# MSP430MCU.net
KiCad netlist of a schematic drawn in Altium Designer
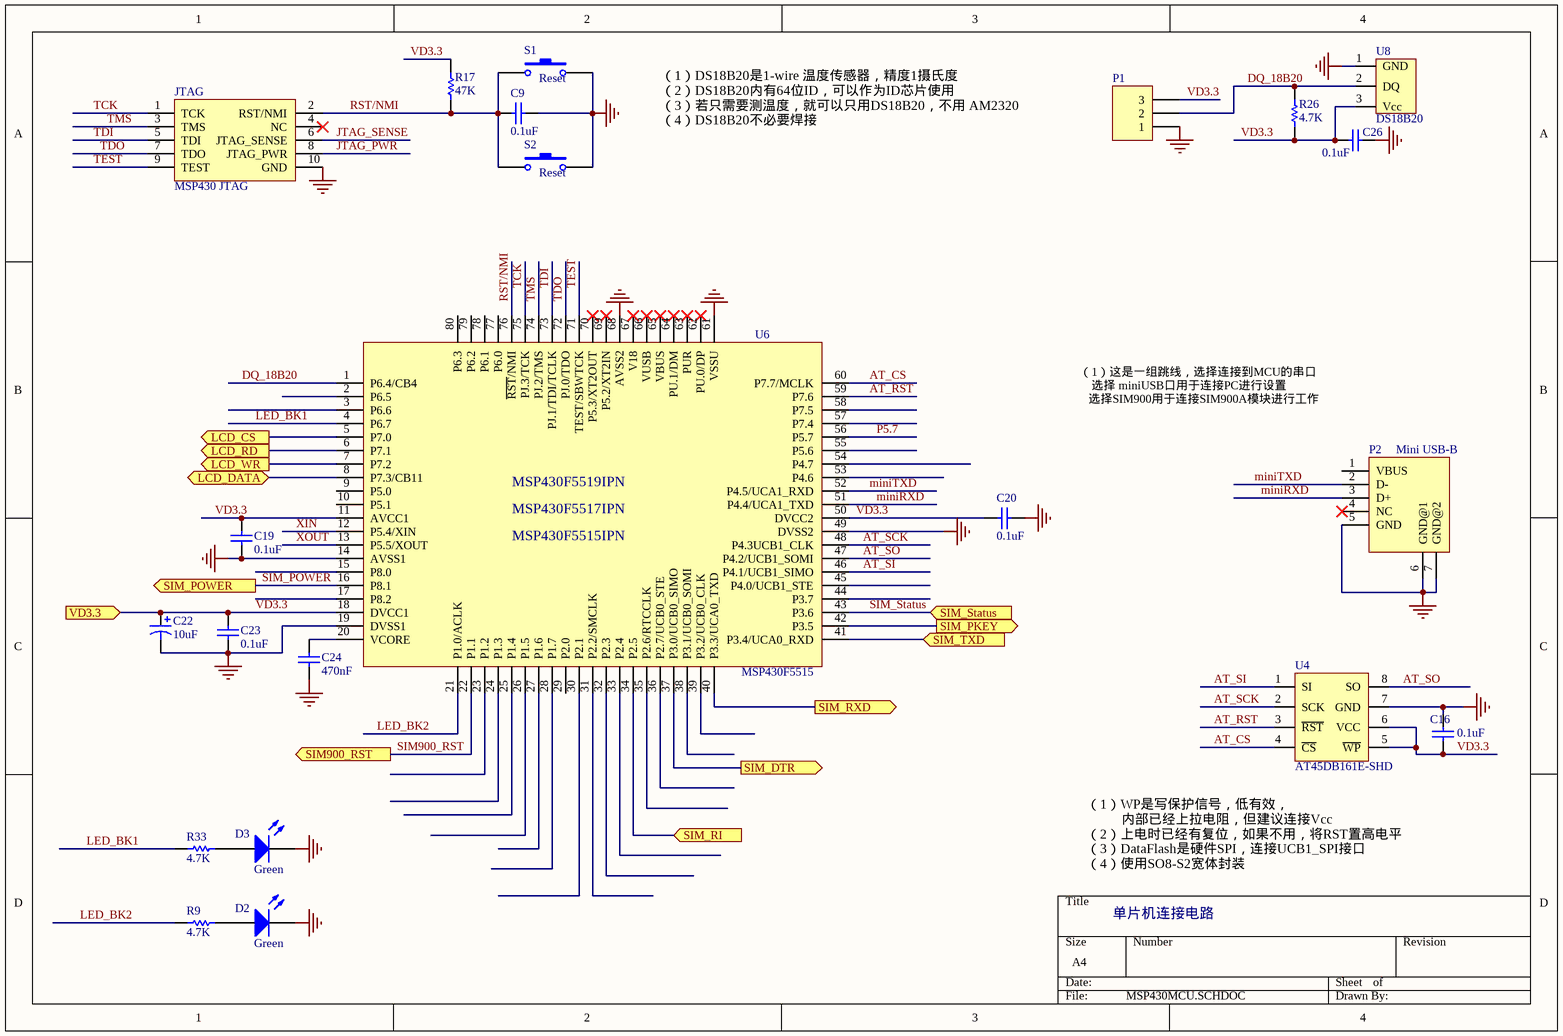
[diagram p0: MSP430MCU.SCHDOC]

(export (version "E")
  (design (tool "Eeschema 10.0.6"))
  (components
    (comp (ref "C9")
      (value "0.1uF")
      (footprint "CC1608-0603")
      (description "Capacitor (Semiconductor SIM Model)")
      (fields (field (name "Comment") "Cap Semi") (field (name "PUBLISHER") "Altium Limited"))
      (libsource (lib "Miscellaneous Devices") (part "Cap Semi"))
    )
    (comp (ref "C16")
      (value "0.1uF")
      (footprint "CC1608-0603")
      (description "Capacitor (Semiconductor SIM Model)")
      (fields (field (name "Comment") "Cap Semi") (field (name "PUBLISHER") "Altium Limited"))
      (libsource (lib "Miscellaneous Devices") (part "Cap Semi"))
    )
    (comp (ref "C19")
      (value "0.1uF")
      (footprint "CC1608-0603")
      (description "Capacitor (Semiconductor SIM Model)")
      (fields (field (name "Comment") "Cap Semi") (field (name "PUBLISHER") "Altium Limited"))
      (libsource (lib "Miscellaneous Devices") (part "Cap Semi"))
    )
    (comp (ref "C20")
      (value "0.1uF")
      (footprint "CC1608-0603")
      (description "Capacitor (Semiconductor SIM Model)")
      (fields (field (name "Comment") "Cap Semi") (field (name "PUBLISHER") "Altium Limited"))
      (libsource (lib "Miscellaneous Devices") (part "Cap Semi"))
    )
    (comp (ref "C22")
      (value "10uF")
      (footprint "CC3216-1206")
      (description "Polarized Capacitor (Surface Mount)")
      (fields (field (name "Comment") "Cap Pol3") (field (name "PUBLISHER") "Altium Limited"))
      (libsource (lib "Miscellaneous Devices") (part "Cap Pol3"))
    )
    (comp (ref "C23")
      (value "0.1uF")
      (footprint "CC1608-0603")
      (description "Capacitor (Semiconductor SIM Model)")
      (fields (field (name "Comment") "Cap Semi") (field (name "PUBLISHER") "Altium Limited"))
      (libsource (lib "Miscellaneous Devices") (part "Cap Semi"))
    )
    (comp (ref "C24")
      (value "470nF")
      (footprint "CC1608-0603")
      (description "Capacitor (Semiconductor SIM Model)")
      (fields (field (name "Comment") "Cap Semi") (field (name "PUBLISHER") "Altium Limited"))
      (libsource (lib "Miscellaneous Devices") (part "Cap Semi"))
    )
    (comp (ref "C26")
      (value "0.1uF")
      (footprint "CC1608-0603")
      (description "Capacitor (Semiconductor SIM Model)")
      (fields (field (name "Comment") "Cap Semi") (field (name "PUBLISHER") "Altium Limited"))
      (libsource (lib "Miscellaneous Devices") (part "Cap Semi"))
    )
    (comp (ref "D2")
      (value "Green")
      (footprint "CC1608-0603")
      (description "Typical RED, GREEN, YELLOW, AMBER GaAs LED")
      (fields (field (name "PUBLISHER") "Altium Limited"))
      (libsource (lib "Miscellaneous Devices") (part "LED2"))
    )
    (comp (ref "D3")
      (value "Green")
      (footprint "CC1608-0603")
      (description "Typical RED, GREEN, YELLOW, AMBER GaAs LED")
      (fields (field (name "PUBLISHER") "Altium Limited"))
      (libsource (lib "Miscellaneous Devices") (part "LED2"))
    )
    (comp (ref "JTAG")
      (value "MSP430 JTAG")
      (footprint "Header10_2mm")
      (libsource (lib "TianYuan") (part "MSP430_JTAG2mm"))
    )
    (comp (ref "P1")
      (value "Header 3")
      (footprint "HDR1X3")
      (description "Header, 3-Pin")
      (fields (field (name "PUBLISHER") "Altium Limited"))
      (libsource (lib "Miscellaneous Connectors") (part "Header 3"))
    )
    (comp (ref "P2")
      (value "Mini USB-B")
      (footprint "MiniUSB-SOP")
      (libsource (lib "TianYuan") (part "Mini USB-B"))
    )
    (comp (ref "R9")
      (value "4.7K")
      (footprint "CR1608-0603")
      (description "Semiconductor Resistor")
      (fields (field (name "Comment") "Res Semi") (field (name "PUBLISHER") "Altium Limited"))
      (libsource (lib "Miscellaneous Devices") (part "Res Semi"))
    )
    (comp (ref "R17")
      (value "47K")
      (footprint "CR1608-0603")
      (description "Semiconductor Resistor")
      (fields (field (name "Comment") "Res Semi") (field (name "PUBLISHER") "Altium Limited"))
      (libsource (lib "Miscellaneous Devices") (part "Res Semi"))
    )
    (comp (ref "R26")
      (value "4.7K")
      (footprint "CR1608-0603")
      (description "Semiconductor Resistor")
      (fields (field (name "Comment") "Res Semi") (field (name "PUBLISHER") "Altium Limited"))
      (libsource (lib "Miscellaneous Devices") (part "Res Semi"))
    )
    (comp (ref "R33")
      (value "4.7K")
      (footprint "CR1608-0603")
      (description "Semiconductor Resistor")
      (fields (field (name "Comment") "Res Semi") (field (name "PUBLISHER") "Altium Limited"))
      (libsource (lib "Miscellaneous Devices") (part "Res Semi"))
    )
    (comp (ref "S1")
      (value "Reset")
      (footprint "KEY_SOT")
      (description "Switch")
      (fields (field (name "PUBLISHER") "Altium Limited"))
      (libsource (lib "Miscellaneous Devices") (part "SW-PB"))
    )
    (comp (ref "S2")
      (value "Reset")
      (footprint "KEY_SOT")
      (description "Switch")
      (fields (field (name "PUBLISHER") "Altium Limited"))
      (libsource (lib "Miscellaneous Devices") (part "SW-PB"))
    )
    (comp (ref "U4")
      (value "AT45DB161E-SHD")
      (footprint "SOIC8-AT45DB-S2")
      (description "16MBits Dataflash")
      (libsource (lib "GanWei09") (part "AT45DB161D"))
    )
    (comp (ref "U6")
      (value "MSP430F5515")
      (footprint "PN80-MSP430F5519")
      (description "MSP430F5519/17/15")
      (libsource (lib "TianYuan") (part "MSP430F5519"))
    )
    (comp (ref "U8")
      (value "DS18B20")
      (footprint "TO-92")
      (description "1-Wire Digital Thermometer")
      (libsource (lib "GanWei09") (part "DS18B20"))
    )
  )
  (nets
    (net (code "1") (name "/AT_CS") (class "Default")
      (node (ref "U4") (pin "4") (pinfunction "~{CS}_4") (pintype "passive"))
      (node (ref "U6") (pin "60") (pinfunction "P7.7/MCLK_60") (pintype "passive"))
    )
    (net (code "2") (name "/AT_RST") (class "Default")
      (node (ref "U4") (pin "3") (pinfunction "~{RST}_3") (pintype "passive"))
      (node (ref "U6") (pin "59") (pinfunction "P7.6_59") (pintype "passive"))
    )
    (net (code "3") (name "/AT_SCK") (class "Default")
      (node (ref "U4") (pin "2") (pinfunction "SCK_2") (pintype "passive"))
      (node (ref "U6") (pin "48") (pinfunction "P4.3UCB1_CLK_48") (pintype "passive"))
    )
    (net (code "4") (name "/AT_SI") (class "Default")
      (node (ref "U4") (pin "1") (pinfunction "SI_1") (pintype "passive"))
      (node (ref "U6") (pin "46") (pinfunction "P4.1/UCB1_SIMO_46") (pintype "passive"))
    )
    (net (code "5") (name "/AT_SO") (class "Default")
      (node (ref "U4") (pin "8") (pinfunction "SO_8") (pintype "passive"))
      (node (ref "U6") (pin "47") (pinfunction "P4.2/UCB1_SOMI_47") (pintype "passive"))
    )
    (net (code "6") (name "/DQ_18B20") (class "Default")
      (node (ref "P1") (pin "2") (pinfunction "2_2") (pintype "passive"))
      (node (ref "R26") (pin "1") (pinfunction "1_1") (pintype "passive"))
      (node (ref "U6") (pin "1") (pinfunction "P6.4/CB4_1") (pintype "passive"))
      (node (ref "U8") (pin "2") (pinfunction "DQ_2") (pintype "passive"))
    )
    (net (code "7") (name "/JTAG_PWR") (class "Default")
      (node (ref "JTAG") (pin "8") (pinfunction "JTAG_PWR_8") (pintype "passive"))
    )
    (net (code "8") (name "/JTAG_SENSE") (class "Default")
      (node (ref "JTAG") (pin "6") (pinfunction "JTAG_SENSE_6") (pintype "passive"))
    )
    (net (code "9") (name "/LCD_CS") (class "Default")
      (node (ref "U6") (pin "5") (pinfunction "P7.0_5") (pintype "passive"))
    )
    (net (code "10") (name "/LCD_DATA") (class "Default")
      (node (ref "U6") (pin "8") (pinfunction "P7.3/CB11_8") (pintype "passive"))
    )
    (net (code "11") (name "/LCD_RD") (class "Default")
      (node (ref "U6") (pin "6") (pinfunction "P7.1_6") (pintype "passive"))
    )
    (net (code "12") (name "/LCD_WR") (class "Default")
      (node (ref "U6") (pin "7") (pinfunction "P7.2_7") (pintype "passive"))
    )
    (net (code "13") (name "/LED_BK1") (class "Default")
      (node (ref "R33") (pin "1") (pinfunction "1_1") (pintype "passive"))
      (node (ref "U6") (pin "4") (pinfunction "P6.7_4") (pintype "passive"))
    )
    (net (code "14") (name "/LED_BK2") (class "Default")
      (node (ref "R9") (pin "1") (pinfunction "1_1") (pintype "passive"))
      (node (ref "U6") (pin "21") (pinfunction "P1.0/ACLK_21") (pintype "passive"))
    )
    (net (code "15") (name "/P5.7") (class "Default")
      (node (ref "U6") (pin "56") (pinfunction "P5.7_56") (pintype "passive"))
    )
    (net (code "16") (name "/RST{slash}NMI") (class "Default")
      (node (ref "C9") (pin "1") (pinfunction "1_1") (pintype "passive"))
      (node (ref "JTAG") (pin "2") (pinfunction "RST/NMI_2") (pintype "passive"))
      (node (ref "R17") (pin "1") (pinfunction "1_1") (pintype "passive"))
      (node (ref "S1") (pin "1") (pinfunction "1_1") (pintype "passive"))
      (node (ref "S2") (pin "1") (pinfunction "1_1") (pintype "passive"))
      (node (ref "U6") (pin "76") (pinfunction "~{RST}/NMI_76") (pintype "passive"))
    )
    (net (code "17") (name "/SIM900_RST") (class "Default")
      (node (ref "U6") (pin "22") (pinfunction "P1.1_22") (pintype "passive"))
    )
    (net (code "18") (name "/SIM_DTR") (class "Default")
      (node (ref "U6") (pin "37") (pinfunction "P3.0/UCB0_SIMO_37") (pintype "passive"))
    )
    (net (code "19") (name "/SIM_PKEY") (class "Default")
      (node (ref "U6") (pin "42") (pinfunction "P3.5_42") (pintype "passive"))
    )
    (net (code "20") (name "/SIM_POWER") (class "Default")
      (node (ref "U6") (pin "16") (pinfunction "P8.1_16") (pintype "passive"))
    )
    (net (code "21") (name "/SIM_RI") (class "Default")
      (node (ref "U6") (pin "34") (pinfunction "P2.5_34") (pintype "passive"))
    )
    (net (code "22") (name "/SIM_RXD") (class "Default")
      (node (ref "U6") (pin "40") (pinfunction "P3.3/UCA0_TXD_40") (pintype "passive"))
    )
    (net (code "23") (name "/SIM_Status") (class "Default")
      (node (ref "U6") (pin "43") (pinfunction "P3.6_43") (pintype "passive"))
    )
    (net (code "24") (name "/SIM_TXD") (class "Default")
      (node (ref "U6") (pin "41") (pinfunction "P3.4/UCA0_RXD_41") (pintype "passive"))
    )
    (net (code "25") (name "/TCK") (class "Default")
      (node (ref "JTAG") (pin "1") (pinfunction "TCK_1") (pintype "passive"))
      (node (ref "U6") (pin "75") (pinfunction "PJ.3/TCK_75") (pintype "passive"))
    )
    (net (code "26") (name "/TDI") (class "Default")
      (node (ref "JTAG") (pin "5") (pinfunction "TDI_5") (pintype "passive"))
      (node (ref "U6") (pin "73") (pinfunction "PJ.1/TDI/TCLK_73") (pintype "passive"))
    )
    (net (code "27") (name "/TDO") (class "Default")
      (node (ref "JTAG") (pin "7") (pinfunction "TDO_7") (pintype "passive"))
      (node (ref "U6") (pin "72") (pinfunction "PJ.0/TDO_72") (pintype "passive"))
    )
    (net (code "28") (name "/TEST") (class "Default")
      (node (ref "JTAG") (pin "9") (pinfunction "TEST_9") (pintype "passive"))
      (node (ref "U6") (pin "71") (pinfunction "TEST/SBWTCK_71") (pintype "passive"))
    )
    (net (code "29") (name "/TMS") (class "Default")
      (node (ref "JTAG") (pin "3") (pinfunction "TMS_3") (pintype "passive"))
      (node (ref "U6") (pin "74") (pinfunction "PJ.2/TMS_74") (pintype "passive"))
    )
    (net (code "30") (name "/VD3.3") (class "Default")
      (node (ref "C16") (pin "1") (pinfunction "1_1") (pintype "passive"))
      (node (ref "C19") (pin "2") (pinfunction "2_2") (pintype "passive"))
      (node (ref "C20") (pin "1") (pinfunction "1_1") (pintype "passive"))
      (node (ref "C22") (pin "1") (pinfunction "1_1") (pintype "passive"))
      (node (ref "C23") (pin "2") (pinfunction "2_2") (pintype "passive"))
      (node (ref "C26") (pin "2") (pinfunction "2_2") (pintype "passive"))
      (node (ref "P1") (pin "3") (pinfunction "3_3") (pintype "passive"))
      (node (ref "R17") (pin "2") (pinfunction "2_2") (pintype "passive"))
      (node (ref "R26") (pin "2") (pinfunction "2_2") (pintype "passive"))
      (node (ref "U4") (pin "5") (pinfunction "~{WP}_5") (pintype "passive"))
      (node (ref "U4") (pin "6") (pinfunction "VCC_6") (pintype "passive"))
      (node (ref "U6") (pin "11") (pinfunction "AVCC1_11") (pintype "passive"))
      (node (ref "U6") (pin "18") (pinfunction "DVCC1_18") (pintype "passive"))
      (node (ref "U6") (pin "50") (pinfunction "DVCC2_50") (pintype "passive"))
      (node (ref "U8") (pin "3") (pinfunction "Vcc_3") (pintype "passive"))
    )
    (net (code "31") (name "/XIN") (class "Default")
      (node (ref "U6") (pin "12") (pinfunction "P5.4/XIN_12") (pintype "passive"))
    )
    (net (code "32") (name "/XOUT") (class "Default")
      (node (ref "U6") (pin "13") (pinfunction "P5.5/XOUT_13") (pintype "passive"))
    )
    (net (code "33") (name "/miniRXD") (class "Default")
      (node (ref "P2") (pin "3") (pinfunction "D+_3") (pintype "passive"))
      (node (ref "U6") (pin "51") (pinfunction "P4.4/UCA1_TXD_51") (pintype "passive"))
    )
    (net (code "34") (name "/miniTXD") (class "Default")
      (node (ref "P2") (pin "2") (pinfunction "D-_2") (pintype "passive"))
      (node (ref "U6") (pin "52") (pinfunction "P4.5/UCA1_RXD_52") (pintype "passive"))
    )
    (net (code "35") (name "GND") (class "Default")
      (node (ref "C16") (pin "2") (pinfunction "2_2") (pintype "passive"))
      (node (ref "C19") (pin "1") (pinfunction "1_1") (pintype "passive"))
      (node (ref "C20") (pin "2") (pinfunction "2_2") (pintype "passive"))
      (node (ref "C22") (pin "2") (pinfunction "2_2") (pintype "passive"))
      (node (ref "C23") (pin "1") (pinfunction "1_1") (pintype "passive"))
      (node (ref "C24") (pin "1") (pinfunction "1_1") (pintype "passive"))
      (node (ref "C26") (pin "1") (pinfunction "1_1") (pintype "passive"))
      (node (ref "C9") (pin "2") (pinfunction "2_2") (pintype "passive"))
      (node (ref "D2") (pin "2") (pinfunction "K_2") (pintype "passive"))
      (node (ref "D3") (pin "2") (pinfunction "K_2") (pintype "passive"))
      (node (ref "JTAG") (pin "10") (pinfunction "GND_10") (pintype "passive"))
      (node (ref "P1") (pin "1") (pinfunction "1_1") (pintype "passive"))
      (node (ref "P2") (pin "5") (pinfunction "GND_5") (pintype "passive"))
      (node (ref "P2") (pin "6") (pinfunction "GND@1_6") (pintype "passive"))
      (node (ref "P2") (pin "7") (pinfunction "GND@2_7") (pintype "passive"))
      (node (ref "S1") (pin "2") (pinfunction "2_2") (pintype "passive"))
      (node (ref "S2") (pin "2") (pinfunction "2_2") (pintype "passive"))
      (node (ref "U4") (pin "7") (pinfunction "GND_7") (pintype "passive"))
      (node (ref "U6") (pin "14") (pinfunction "AVSS1_14") (pintype "passive"))
      (node (ref "U6") (pin "19") (pinfunction "DVSS1_19") (pintype "passive"))
      (node (ref "U6") (pin "49") (pinfunction "DVSS2_49") (pintype "passive"))
      (node (ref "U6") (pin "61") (pinfunction "VSSU_61") (pintype "passive"))
      (node (ref "U6") (pin "68") (pinfunction "AVSS2_68") (pintype "passive"))
      (node (ref "U8") (pin "1") (pinfunction "GND_1") (pintype "passive"))
    )
    (net (code "36") (name "Net-(D2-A)") (class "Default")
      (node (ref "D2") (pin "1") (pinfunction "A_1") (pintype "passive"))
      (node (ref "R9") (pin "2") (pinfunction "2_2") (pintype "passive"))
    )
    (net (code "37") (name "Net-(D3-A)") (class "Default")
      (node (ref "D3") (pin "1") (pinfunction "A_1") (pintype "passive"))
      (node (ref "R33") (pin "2") (pinfunction "2_2") (pintype "passive"))
    )
    (net (code "38") (name "Net-(U6-VCORE)") (class "Default")
      (node (ref "C24") (pin "2") (pinfunction "2_2") (pintype "passive"))
      (node (ref "U6") (pin "20") (pinfunction "VCORE_20") (pintype "passive"))
    )
    (net (code "39") (name "unconnected-(JTAG-NC-Pad4)") (class "Default")
      (node (ref "JTAG") (pin "4") (pinfunction "NC_4") (pintype "passive+no_connect"))
    )
    (net (code "40") (name "unconnected-(P2-NC-Pad4)") (class "Default")
      (node (ref "P2") (pin "4") (pinfunction "NC_4") (pintype "passive+no_connect"))
    )
    (net (code "41") (name "unconnected-(P2-VBUS-Pad1)") (class "Default")
      (node (ref "P2") (pin "1") (pinfunction "VBUS_1") (pintype "passive"))
    )
    (net (code "42") (name "unconnected-(U6-P1.2-Pad23)") (class "Default")
      (node (ref "U6") (pin "23") (pinfunction "P1.2_23") (pintype "passive"))
    )
    (net (code "43") (name "unconnected-(U6-P1.3-Pad24)") (class "Default")
      (node (ref "U6") (pin "24") (pinfunction "P1.3_24") (pintype "passive"))
    )
    (net (code "44") (name "unconnected-(U6-P1.4-Pad25)") (class "Default")
      (node (ref "U6") (pin "25") (pinfunction "P1.4_25") (pintype "passive"))
    )
    (net (code "45") (name "unconnected-(U6-P1.5-Pad26)") (class "Default")
      (node (ref "U6") (pin "26") (pinfunction "P1.5_26") (pintype "passive"))
    )
    (net (code "46") (name "unconnected-(U6-P1.6-Pad27)") (class "Default")
      (node (ref "U6") (pin "27") (pinfunction "P1.6_27") (pintype "passive"))
    )
    (net (code "47") (name "unconnected-(U6-P1.7-Pad28)") (class "Default")
      (node (ref "U6") (pin "28") (pinfunction "P1.7_28") (pintype "passive"))
    )
    (net (code "48") (name "unconnected-(U6-P2.0-Pad29)") (class "Default")
      (node (ref "U6") (pin "29") (pinfunction "P2.0_29") (pintype "passive"))
    )
    (net (code "49") (name "unconnected-(U6-P2.1-Pad30)") (class "Default")
      (node (ref "U6") (pin "30") (pinfunction "P2.1_30") (pintype "passive"))
    )
    (net (code "50") (name "unconnected-(U6-P2.2{slash}SMCLK-Pad31)") (class "Default")
      (node (ref "U6") (pin "31") (pinfunction "P2.2/SMCLK_31") (pintype "passive"))
    )
    (net (code "51") (name "unconnected-(U6-P2.3-Pad32)") (class "Default")
      (node (ref "U6") (pin "32") (pinfunction "P2.3_32") (pintype "passive"))
    )
    (net (code "52") (name "unconnected-(U6-P2.4-Pad33)") (class "Default")
      (node (ref "U6") (pin "33") (pinfunction "P2.4_33") (pintype "passive"))
    )
    (net (code "53") (name "unconnected-(U6-P2.6{slash}RTCCLK-Pad35)") (class "Default")
      (node (ref "U6") (pin "35") (pinfunction "P2.6/RTCCLK_35") (pintype "passive"))
    )
    (net (code "54") (name "unconnected-(U6-P2.7{slash}UCB0_STE-Pad36)") (class "Default")
      (node (ref "U6") (pin "36") (pinfunction "P2.7/UCB0_STE_36") (pintype "passive"))
    )
    (net (code "55") (name "unconnected-(U6-P3.1{slash}UCB0_SOMI-Pad38)") (class "Default")
      (node (ref "U6") (pin "38") (pinfunction "P3.1/UCB0_SOMI_38") (pintype "passive"))
    )
    (net (code "56") (name "unconnected-(U6-P3.2{slash}UCB0_CLK-Pad39)") (class "Default")
      (node (ref "U6") (pin "39") (pinfunction "P3.2/UCB0_CLK_39") (pintype "passive"))
    )
    (net (code "57") (name "unconnected-(U6-P3.7-Pad44)") (class "Default")
      (node (ref "U6") (pin "44") (pinfunction "P3.7_44") (pintype "passive"))
    )
    (net (code "58") (name "unconnected-(U6-P4.0{slash}UCB1_STE-Pad45)") (class "Default")
      (node (ref "U6") (pin "45") (pinfunction "P4.0/UCB1_STE_45") (pintype "passive"))
    )
    (net (code "59") (name "unconnected-(U6-P4.6-Pad53)") (class "Default")
      (node (ref "U6") (pin "53") (pinfunction "P4.6_53") (pintype "passive"))
    )
    (net (code "60") (name "unconnected-(U6-P4.7-Pad54)") (class "Default")
      (node (ref "U6") (pin "54") (pinfunction "P4.7_54") (pintype "passive"))
    )
    (net (code "61") (name "unconnected-(U6-P5.0-Pad9)") (class "Default")
      (node (ref "U6") (pin "9") (pinfunction "P5.0_9") (pintype "passive"))
    )
    (net (code "62") (name "unconnected-(U6-P5.1-Pad10)") (class "Default")
      (node (ref "U6") (pin "10") (pinfunction "P5.1_10") (pintype "passive"))
    )
    (net (code "63") (name "unconnected-(U6-P5.2{slash}XT2IN-Pad69)") (class "Default")
      (node (ref "U6") (pin "69") (pinfunction "P5.2/XT2IN_69") (pintype "passive+no_connect"))
    )
    (net (code "64") (name "unconnected-(U6-P5.3{slash}XT2OUT-Pad70)") (class "Default")
      (node (ref "U6") (pin "70") (pinfunction "P5.3/XT2OUT_70") (pintype "passive+no_connect"))
    )
    (net (code "65") (name "unconnected-(U6-P5.6-Pad55)") (class "Default")
      (node (ref "U6") (pin "55") (pinfunction "P5.6_55") (pintype "passive"))
    )
    (net (code "66") (name "unconnected-(U6-P6.0-Pad77)") (class "Default")
      (node (ref "U6") (pin "77") (pinfunction "P6.0_77") (pintype "passive"))
    )
    (net (code "67") (name "unconnected-(U6-P6.1-Pad78)") (class "Default")
      (node (ref "U6") (pin "78") (pinfunction "P6.1_78") (pintype "passive"))
    )
    (net (code "68") (name "unconnected-(U6-P6.2-Pad79)") (class "Default")
      (node (ref "U6") (pin "79") (pinfunction "P6.2_79") (pintype "passive"))
    )
    (net (code "69") (name "unconnected-(U6-P6.3-Pad80)") (class "Default")
      (node (ref "U6") (pin "80") (pinfunction "P6.3_80") (pintype "passive"))
    )
    (net (code "70") (name "unconnected-(U6-P6.5-Pad2)") (class "Default")
      (node (ref "U6") (pin "2") (pinfunction "P6.5_2") (pintype "passive"))
    )
    (net (code "71") (name "unconnected-(U6-P6.6-Pad3)") (class "Default")
      (node (ref "U6") (pin "3") (pinfunction "P6.6_3") (pintype "passive"))
    )
    (net (code "72") (name "unconnected-(U6-P7.4-Pad57)") (class "Default")
      (node (ref "U6") (pin "57") (pinfunction "P7.4_57") (pintype "passive"))
    )
    (net (code "73") (name "unconnected-(U6-P7.5-Pad58)") (class "Default")
      (node (ref "U6") (pin "58") (pinfunction "P7.5_58") (pintype "passive"))
    )
    (net (code "74") (name "unconnected-(U6-P8.0-Pad15)") (class "Default")
      (node (ref "U6") (pin "15") (pinfunction "P8.0_15") (pintype "passive"))
    )
    (net (code "75") (name "unconnected-(U6-P8.2-Pad17)") (class "Default")
      (node (ref "U6") (pin "17") (pinfunction "P8.2_17") (pintype "passive"))
    )
    (net (code "76") (name "unconnected-(U6-PU.0{slash}DP-Pad62)") (class "Default")
      (node (ref "U6") (pin "62") (pinfunction "PU.0/DP_62") (pintype "passive+no_connect"))
    )
    (net (code "77") (name "unconnected-(U6-PU.1{slash}DM-Pad64)") (class "Default")
      (node (ref "U6") (pin "64") (pinfunction "PU.1/DM_64") (pintype "passive+no_connect"))
    )
    (net (code "78") (name "unconnected-(U6-PUR-Pad63)") (class "Default")
      (node (ref "U6") (pin "63") (pinfunction "PUR_63") (pintype "passive+no_connect"))
    )
    (net (code "79") (name "unconnected-(U6-V18-Pad67)") (class "Default")
      (node (ref "U6") (pin "67") (pinfunction "V18_67") (pintype "passive+no_connect"))
    )
    (net (code "80") (name "unconnected-(U6-VBUS-Pad65)") (class "Default")
      (node (ref "U6") (pin "65") (pinfunction "VBUS_65") (pintype "passive+no_connect"))
    )
    (net (code "81") (name "unconnected-(U6-VUSB-Pad66)") (class "Default")
      (node (ref "U6") (pin "66") (pinfunction "VUSB_66") (pintype "passive+no_connect"))
    )
  )
)
